# SparkFun_RS323_Shifter.net
KiCad netlist of a schematic drawn in EAGLE
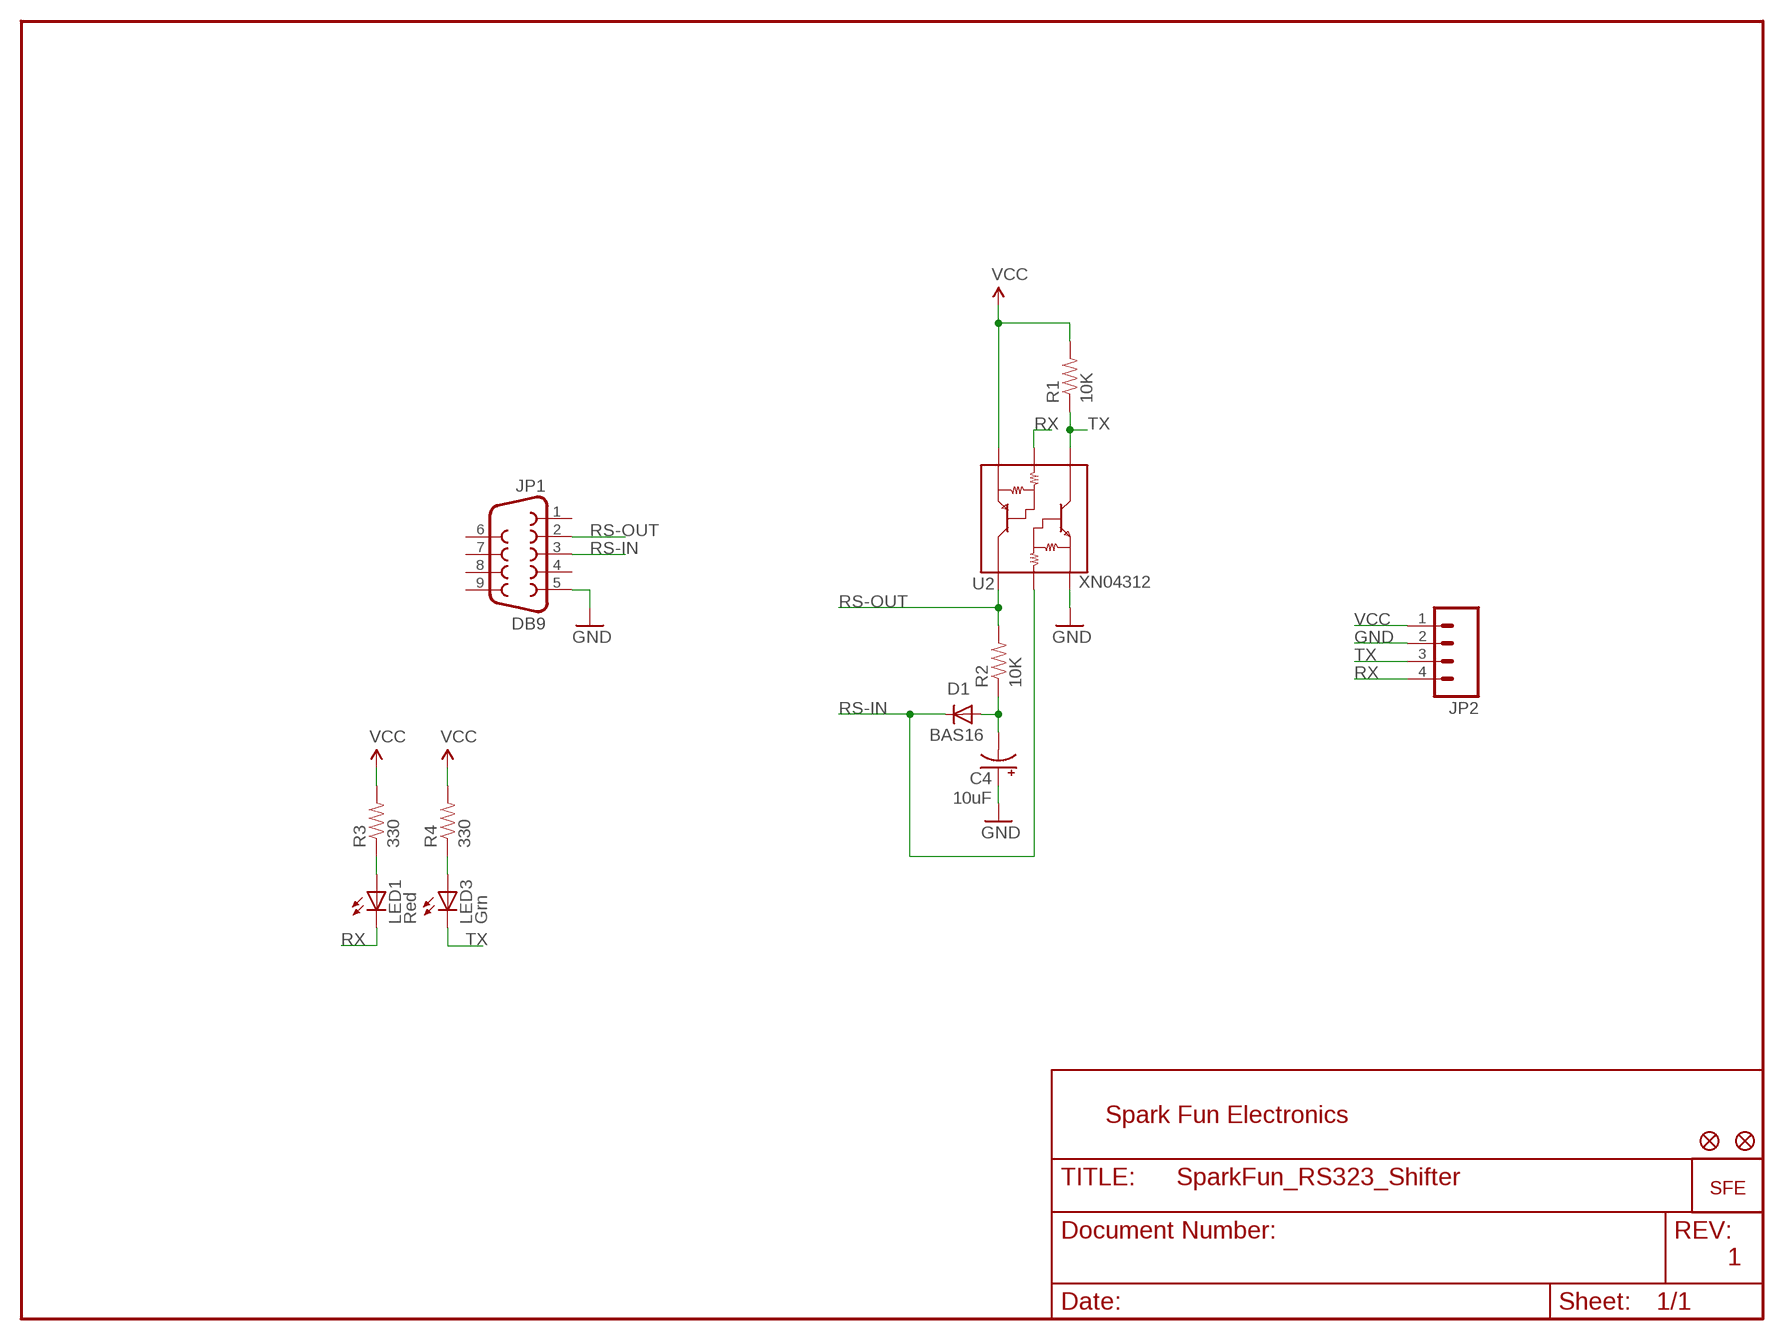
[diagram p0: schematic, sheet 1]

(export (version "E")
  (design (tool "Eeschema 10.0.6"))
  (components
    (comp (ref "C4")
      (value "10uF")
      (footprint "eagle-import:EIA3216")
      (libsource (lib "eagle-import") (part "CAP_POL1206"))
    )
    (comp (ref "D1")
      (value "BAS16")
      (footprint "eagle-import:SOD-323")
      (libsource (lib "eagle-import") (part "DIODESOD"))
    )
    (comp (ref "E$1")
      (value "FIDUCIAL1X2")
      (footprint "eagle-import:FIDUCIAL-1X2")
      (libsource (lib "eagle-import") (part "FIDUCIAL1X2"))
    )
    (comp (ref "E$2")
      (value "FIDUCIAL1X2")
      (footprint "eagle-import:FIDUCIAL-1X2")
      (libsource (lib "eagle-import") (part "FIDUCIAL1X2"))
    )
    (comp (ref "JP1")
      (value "DB9")
      (footprint "eagle-import:DB9")
      (libsource (lib "eagle-import") (part "DB9FEMALE"))
    )
    (comp (ref "JP2")
      (value "M04PTH")
      (footprint "eagle-import:1X04")
      (libsource (lib "eagle-import") (part "M04PTH"))
    )
    (comp (ref "LED1")
      (value "Red")
      (footprint "eagle-import:LED-1206")
      (libsource (lib "eagle-import") (part "LED1206"))
    )
    (comp (ref "LED3")
      (value "Grn")
      (footprint "eagle-import:LED-1206")
      (libsource (lib "eagle-import") (part "LED1206"))
    )
    (comp (ref "R1")
      (value "10K")
      (footprint "eagle-import:0603-RES")
      (libsource (lib "eagle-import") (part "RESISTOR0603-RES"))
    )
    (comp (ref "R2")
      (value "10K")
      (footprint "eagle-import:0603-RES")
      (libsource (lib "eagle-import") (part "RESISTOR0603-RES"))
    )
    (comp (ref "R3")
      (value "330")
      (footprint "eagle-import:0603-RES")
      (libsource (lib "eagle-import") (part "RESISTOR0603-RES"))
    )
    (comp (ref "R4")
      (value "330")
      (footprint "eagle-import:0603-RES")
      (libsource (lib "eagle-import") (part "RESISTOR0603-RES"))
    )
    (comp (ref "U$1")
      (value "LOGO-SFENEW")
      (footprint "eagle-import:SFE-NEW-WEBLOGO")
      (libsource (lib "eagle-import") (part "LOGO-SFENEW"))
    )
    (comp (ref "U2")
      (value "XN04312")
      (footprint "eagle-import:SOT23-6")
      (libsource (lib "eagle-import") (part "XN04312SOT"))
    )
  )
  (nets
    (net (code "1") (name "/RS-IN") (class "Default")
      (node (ref "D1") (pin "1") (pinfunction "C_1") (pintype "passive"))
      (node (ref "JP1") (pin "3") (pinfunction "3_3") (pintype "passive"))
      (node (ref "U2") (pin "5") (pinfunction "B1_5") (pintype "bidirectional"))
    )
    (net (code "2") (name "/RS-OUT") (class "Default")
      (node (ref "JP1") (pin "2") (pinfunction "2_2") (pintype "passive"))
      (node (ref "R2") (pin "2") (pinfunction "2_2") (pintype "passive"))
      (node (ref "U2") (pin "4") (pinfunction "C2_4") (pintype "bidirectional"))
    )
    (net (code "3") (name "/RX") (class "Default")
      (node (ref "JP2") (pin "4") (pinfunction "4_4") (pintype "passive"))
      (node (ref "LED1") (pin "C") (pinfunction "C_C") (pintype "passive"))
      (node (ref "U2") (pin "2") (pinfunction "B2_2") (pintype "bidirectional"))
    )
    (net (code "4") (name "/TX") (class "Default")
      (node (ref "JP2") (pin "3") (pinfunction "3_3") (pintype "passive"))
      (node (ref "LED3") (pin "C") (pinfunction "C_C") (pintype "passive"))
      (node (ref "R1") (pin "1") (pinfunction "1_1") (pintype "passive"))
      (node (ref "U2") (pin "1") (pinfunction "C1_1") (pintype "bidirectional"))
    )
    (net (code "5") (name "GND") (class "Default")
      (node (ref "C4") (pin "A") (pinfunction "+_A") (pintype "passive"))
      (node (ref "JP1") (pin "5") (pinfunction "5_5") (pintype "passive"))
      (node (ref "JP2") (pin "2") (pinfunction "2_2") (pintype "passive"))
      (node (ref "U2") (pin "6") (pinfunction "E1_6") (pintype "bidirectional"))
    )
    (net (code "6") (name "Net-(C4--)") (class "Default")
      (node (ref "C4") (pin "C") (pinfunction "-_C") (pintype "passive"))
      (node (ref "D1") (pin "2") (pinfunction "A_2") (pintype "passive"))
      (node (ref "R2") (pin "1") (pinfunction "1_1") (pintype "passive"))
    )
    (net (code "7") (name "Net-(LED1-PadA)") (class "Default")
      (node (ref "LED1") (pin "A") (pinfunction "A_A") (pintype "passive"))
      (node (ref "R3") (pin "1") (pinfunction "1_1") (pintype "passive"))
    )
    (net (code "8") (name "Net-(LED3-PadA)") (class "Default")
      (node (ref "LED3") (pin "A") (pinfunction "A_A") (pintype "passive"))
      (node (ref "R4") (pin "1") (pinfunction "1_1") (pintype "passive"))
    )
    (net (code "9") (name "VCC") (class "Default")
      (node (ref "JP2") (pin "1") (pinfunction "1_1") (pintype "passive"))
      (node (ref "R1") (pin "2") (pinfunction "2_2") (pintype "passive"))
      (node (ref "R3") (pin "2") (pinfunction "2_2") (pintype "passive"))
      (node (ref "R4") (pin "2") (pinfunction "2_2") (pintype "passive"))
      (node (ref "U2") (pin "3") (pinfunction "E2_3") (pintype "bidirectional"))
    )
    (net (code "10") (name "unconnected-(JP1-Pad1)") (class "Default")
      (node (ref "JP1") (pin "1") (pinfunction "1_1") (pintype "passive"))
    )
    (net (code "11") (name "unconnected-(JP1-Pad4)") (class "Default")
      (node (ref "JP1") (pin "4") (pinfunction "4_4") (pintype "passive"))
    )
    (net (code "12") (name "unconnected-(JP1-Pad6)") (class "Default")
      (node (ref "JP1") (pin "6") (pinfunction "6_6") (pintype "passive"))
    )
    (net (code "13") (name "unconnected-(JP1-Pad7)") (class "Default")
      (node (ref "JP1") (pin "7") (pinfunction "7_7") (pintype "passive"))
    )
    (net (code "14") (name "unconnected-(JP1-Pad8)") (class "Default")
      (node (ref "JP1") (pin "8") (pinfunction "8_8") (pintype "passive"))
    )
    (net (code "15") (name "unconnected-(JP1-Pad9)") (class "Default")
      (node (ref "JP1") (pin "9") (pinfunction "9_9") (pintype "passive"))
    )
  )
)
